# 32-APPLICATION_BOARD_CONNECTOR.net
KiCad netlist of a schematic drawn in Altium Designer
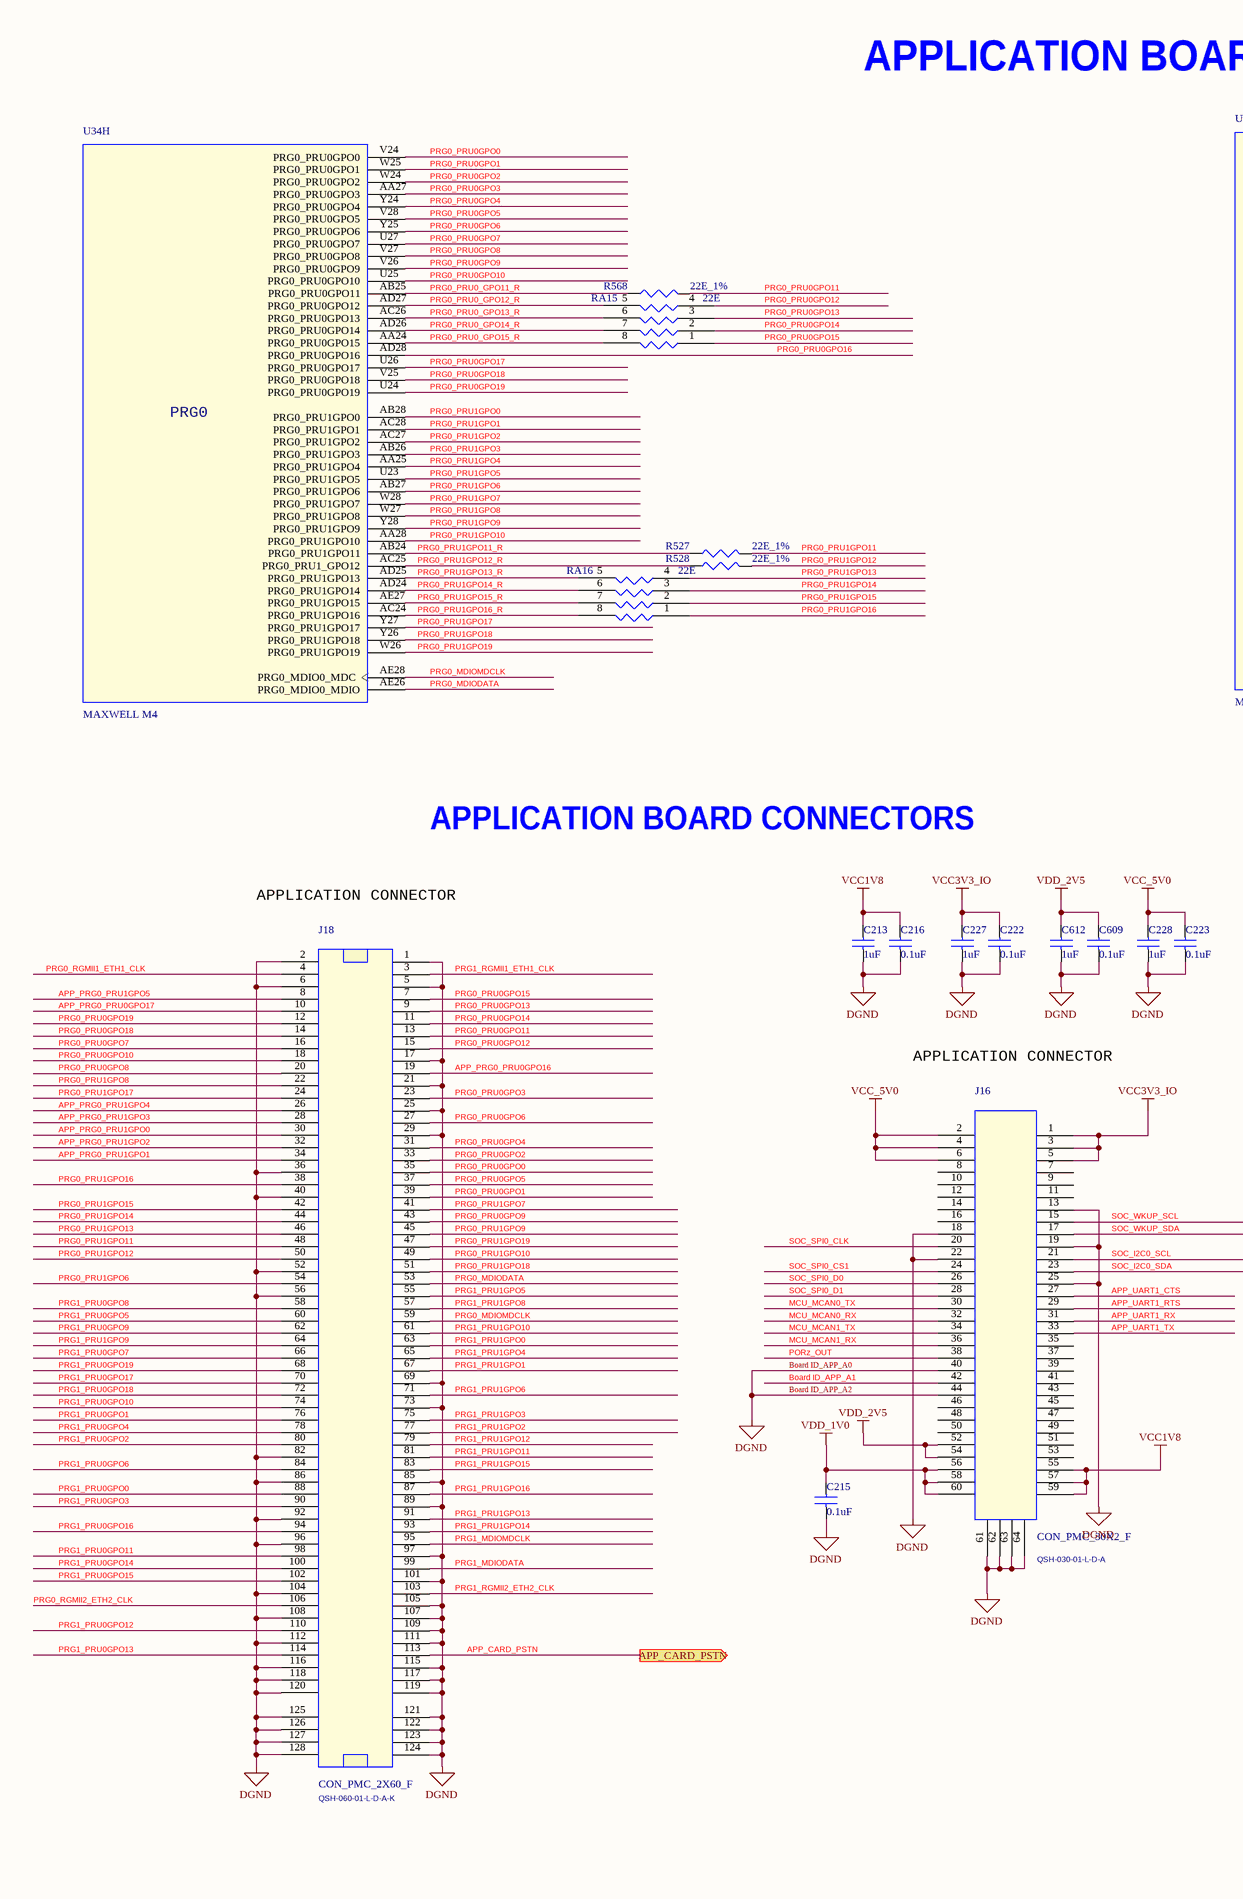
[diagram p0: 32-APPLICATION BOARD CONNECTOR.SchDoc, left]
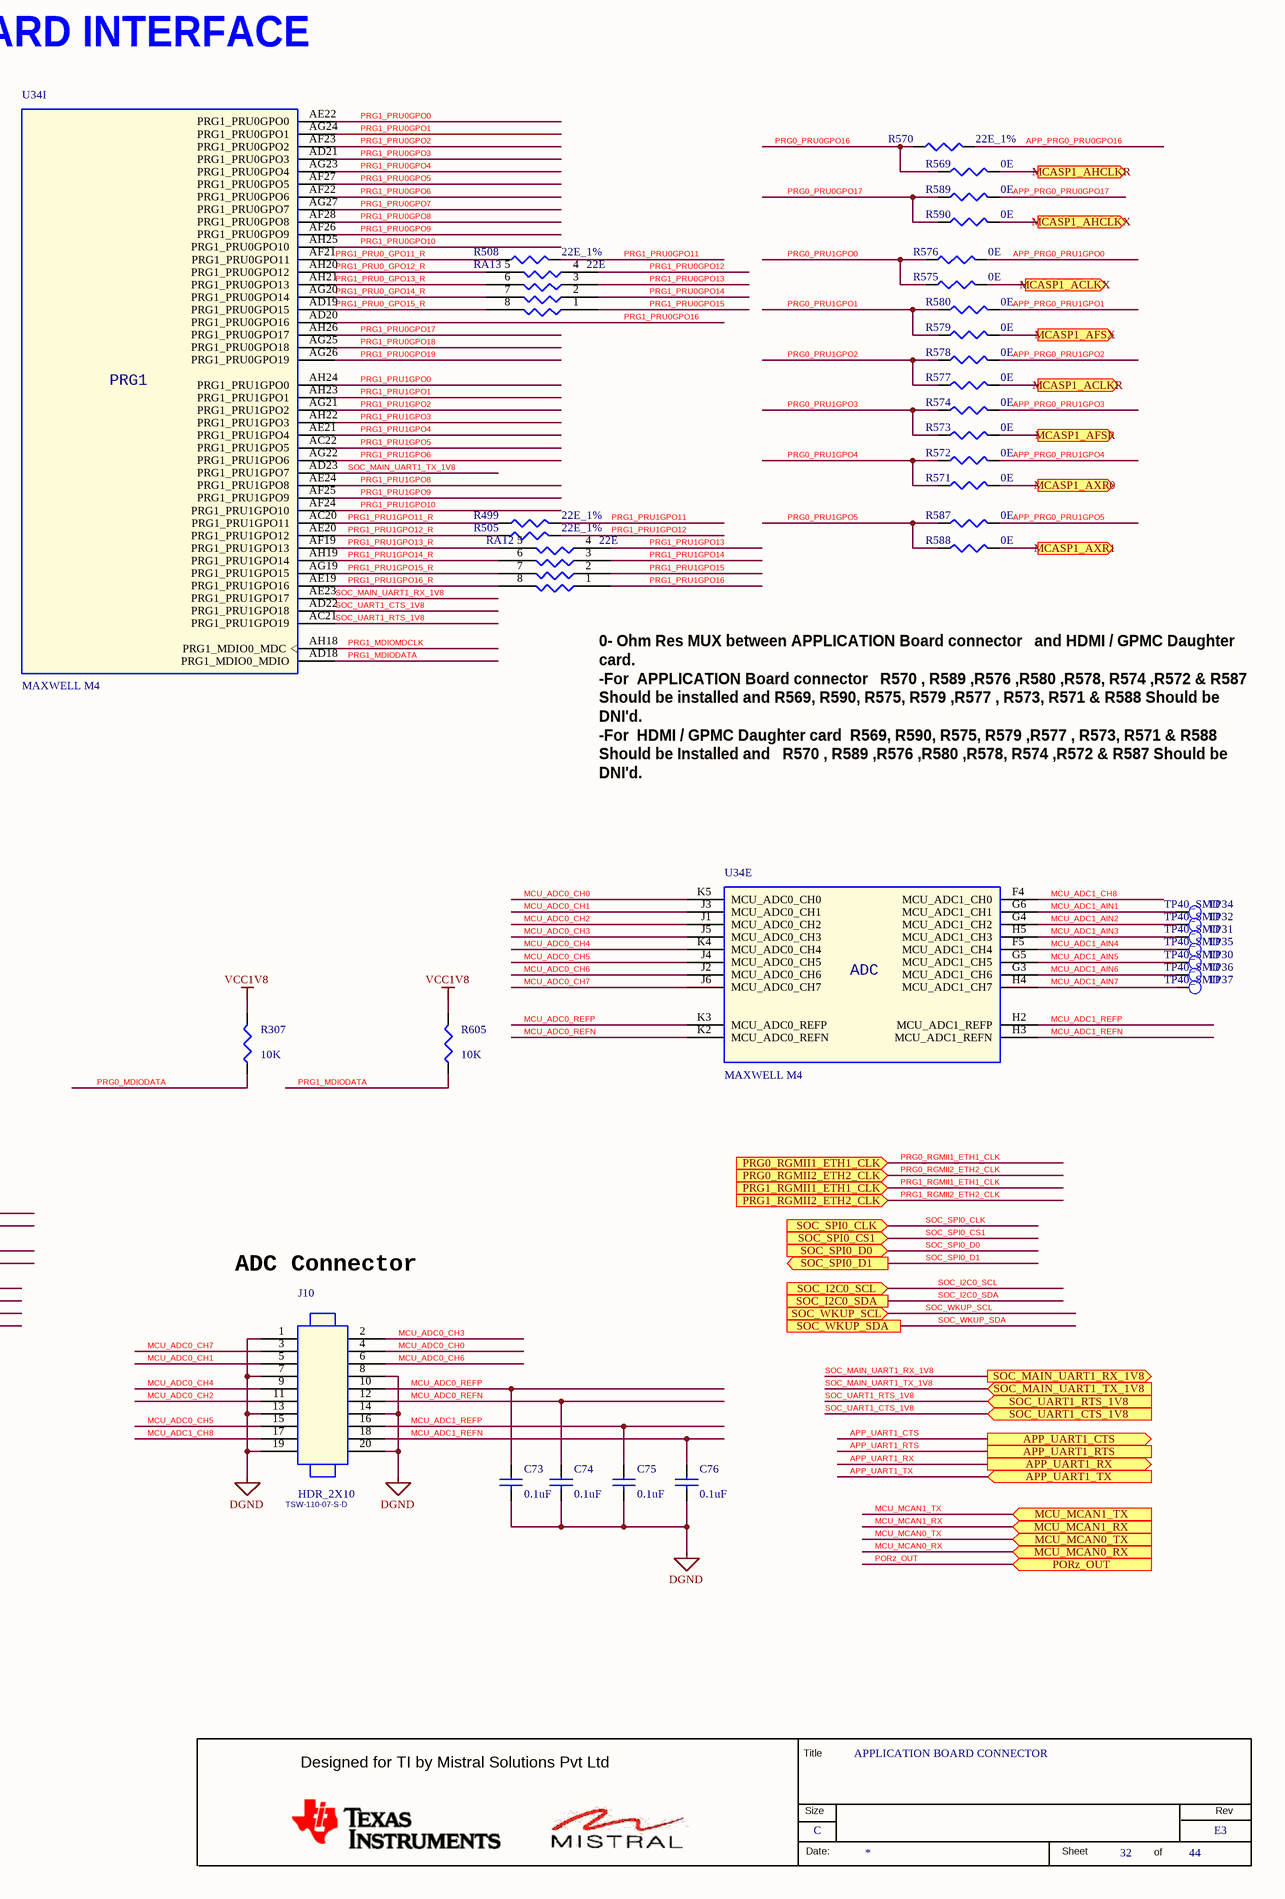
[diagram p1: 32-APPLICATION BOARD CONNECTOR.SchDoc, right]

(export (version "E")
  (design (tool "Eeschema 10.0.6"))
  (components
    (comp (ref "C73")
      (value "0.1uF")
      (footprint "CAP0201_0-5")
      (description "CAP CERAMIC 0.1uF 16V 10% X5R 0201")
      (fields (field (name "DISTRIBUTOR_PART_NUMBER") "490-16742-1-ND") (field (name "VOLTAGE") "16V"))
      (libsource (lib "*") (part "CAP_Dup5"))
    )
    (comp (ref "C74")
      (value "0.1uF")
      (footprint "CAP0201_0-5")
      (description "CAP CERAMIC 0.1uF 16V 10% X5R 0201")
      (fields
        (field (name "MISTRAL PART NO") "120009030072-R")
        (field (name "MFR_PART_NUMBER") "GRM033R61C104KE84J")
      )
      (libsource (lib "*") (part "CAP_Dup5"))
    )
    (comp (ref "C75")
      (value "0.1uF")
      (footprint "CAP0201_0-5")
      (description "CAP CERAMIC 0.1uF 16V 10% X5R 0201")
      (fields (field (name "DISTRIBUTOR_PART_NUMBER") "490-16742-1-ND") (field (name "VOLTAGE") "16V"))
      (libsource (lib "*") (part "CAP_Dup5"))
    )
    (comp (ref "C76")
      (value "0.1uF")
      (footprint "CAP0201_0-5")
      (description "CAP CERAMIC 0.1uF 16V 10% X5R 0201")
      (fields
        (field (name "MISTRAL PART NO") "120009030072-R")
        (field (name "MFR_PART_NUMBER") "GRM033R61C104KE84J")
      )
      (libsource (lib "*") (part "CAP_Dup5"))
    )
    (comp (ref "C213")
      (value "1uF")
      (footprint "CAP0402_0-75")
      (description "CAP CERAMIC 1uF 16V 20% X5R 0402")
      (fields
        (field (name "MISTRAL PART NO") "120018020006-R")
        (field (name "MFR_PART_NUMBER") "EMK105BJ105MV-F")
      )
      (libsource (lib "*") (part "CAP_Dup5"))
    )
    (comp (ref "C215")
      (value "0.1uF")
      (footprint "CAP0201_0-5")
      (description "CAP CERAMIC 0.1uF 16V 10% X5R 0201")
      (fields
        (field (name "MISTRAL PART NO") "120009030072-R")
        (field (name "MFR_PART_NUMBER") "GRM033R61C104KE84J")
      )
      (libsource (lib "*") (part "CAP_Dup5"))
    )
    (comp (ref "C216")
      (value "0.1uF")
      (footprint "CAP0201_0-5")
      (description "CAP CERAMIC 0.1uF 16V 10% X5R 0201")
      (fields (field (name "DISTRIBUTOR_PART_NUMBER") "490-16742-1-ND") (field (name "VOLTAGE") "16V"))
      (libsource (lib "*") (part "CAP_Dup5"))
    )
    (comp (ref "C222")
      (value "0.1uF")
      (footprint "CAP0201_0-5")
      (description "CAP CERAMIC 0.1uF 16V 10% X5R 0201")
      (fields
        (field (name "MISTRAL PART NO") "120009030072-R")
        (field (name "MFR_PART_NUMBER") "GRM033R61C104KE84J")
      )
      (libsource (lib "*") (part "CAP_Dup5"))
    )
    (comp (ref "C223")
      (value "0.1uF")
      (footprint "CAP0201_0-5")
      (description "CAP CERAMIC 0.1uF 16V 10% X5R 0201")
      (fields (field (name "DISTRIBUTOR_PART_NUMBER") "490-16742-1-ND") (field (name "VOLTAGE") "16V"))
      (libsource (lib "*") (part "CAP_Dup5"))
    )
    (comp (ref "C227")
      (value "1uF")
      (footprint "CAP0402_0-75")
      (description "CAP CERAMIC 1uF 16V 20% X5R 0402")
      (fields (field (name "DISTRIBUTOR_PART_NUMBER") "587-5514-1-ND") (field (name "VOLTAGE") "16V"))
      (libsource (lib "*") (part "CAP_Dup5"))
    )
    (comp (ref "C228")
      (value "1uF")
      (footprint "CAP0402_0-75")
      (description "CAP CERAMIC 1uF 16V 20% X5R 0402")
      (fields
        (field (name "MISTRAL PART NO") "120018020006-R")
        (field (name "MFR_PART_NUMBER") "EMK105BJ105MV-F")
      )
      (libsource (lib "*") (part "CAP_Dup5"))
    )
    (comp (ref "C609")
      (value "0.1uF")
      (footprint "CAP0201_0-5")
      (description "CAP CERAMIC 0.1uF 16V 10% X5R 0201")
      (fields
        (field (name "MISTRAL PART NO") "120009030072-R")
        (field (name "MFR_PART_NUMBER") "GRM033R61C104KE84J")
      )
      (libsource (lib "*") (part "CAP_Dup5"))
    )
    (comp (ref "C612")
      (value "1uF")
      (footprint "CAP0402_0-75")
      (description "CAP CERAMIC 1uF 16V 20% X5R 0402")
      (fields
        (field (name "MISTRAL PART NO") "120018020006-R")
        (field (name "MFR_PART_NUMBER") "EMK105BJ105MV-F")
      )
      (libsource (lib "*") (part "CAP_Dup5"))
    )
    (comp (ref "J10")
      (value "HDR_2X10")
      (footprint "HDR_2X10_TSW_100_S_T")
      (description "CON HDR 2X10 2.54MM PITCH ST TH")
      (fields
        (field (name "DISTRIBUTOR_PART_NUMBER") "SAM1032-10-ND")
        (field (name "VOLTAGE") "NA")
        (field (name "MFR_PART_NUMBER") "TSW-110-07-S-D")
      )
      (libsource (lib "*") (part "HEADER_10X2"))
    )
    (comp (ref "J16")
      (value "CON_PMC_30X2_F")
      (footprint "CON_PMC30X2_QSH-030-01-L_S_S_S")
      (description "CON PMC 30X2 0.50MM PITCH FEMALE ST SMD")
      (fields
        (field (name "MISTRAL PART NO") "150009030606")
        (field (name "MFR_PART_NUMBER") "QSH-030-01-L-D-A")
      )
      (libsource (lib "*") (part "CON_PMC_30X2_F_Dup1"))
    )
    (comp (ref "J18")
      (value "CON_PMC_2X60_F")
      (footprint "CON_PMC60X2_HQCD-060_S_S_S_3-3")
      (description "CON PMC 2X60 0.50MM PITCH FEMALE ST SMD")
      (fields
        (field (name "MISTRAL PART NO") "150010060004-R")
        (field (name "MFR_PART_NUMBER") "QSH-060-01-L-D-A-K")
        (field (name "TOLERANCE") "NA")
      )
      (libsource (lib "*") (part "CON_PMC_60X2_HQCD"))
    )
    (comp (ref "R307")
      (value "10K")
      (footprint "RES0402_0-5")
      (description "RES 10K 1/16W 5% 0402")
      (fields
        (field (name "MISTRAL PART NO") "110009030208-R")
        (field (name "MFR_PART_NUMBER") "RC0402JR-0710KL")
      )
      (libsource (lib "*") (part "RESISTOR_Dup5"))
    )
    (comp (ref "R499")
      (value "22E_1%")
      (footprint "RES0402")
      (description "RES 22E 1/16W 1% 0402")
      (fields
        (field (name "MISTRAL PART NO") "110009090004-P")
        (field (name "MFR_PART_NUMBER") "RC0402FR-0722RL")
      )
      (libsource (lib "*") (part "RESISTOR_Dup5"))
    )
    (comp (ref "R505")
      (value "22E_1%")
      (footprint "RES0402")
      (description "RES 22E 1/16W 1% 0402")
      (fields
        (field (name "CUST_PART_NUMBER") "4700-80047E")
        (field (name "DISTRIBUTOR_PART_NUMBER") "311-22.0LRCT-ND")
      )
      (libsource (lib "*") (part "RESISTOR_Dup5"))
    )
    (comp (ref "R508")
      (value "22E_1%")
      (footprint "RES0402")
      (description "RES 22E 1/16W 1% 0402")
      (fields
        (field (name "MISTRAL PART NO") "110009090004-P")
        (field (name "MFR_PART_NUMBER") "RC0402FR-0722RL")
      )
      (libsource (lib "*") (part "RESISTOR_Dup5"))
    )
    (comp (ref "R527")
      (value "22E_1%")
      (footprint "RES0402")
      (description "RES 22E 1/16W 1% 0402")
      (fields
        (field (name "MISTRAL PART NO") "110009090004-P")
        (field (name "MFR_PART_NUMBER") "RC0402FR-0722RL")
      )
      (libsource (lib "*") (part "RESISTOR_Dup5"))
    )
    (comp (ref "R528")
      (value "22E_1%")
      (footprint "RES0402")
      (description "RES 22E 1/16W 1% 0402")
      (fields
        (field (name "MISTRAL PART NO") "110009090004-P")
        (field (name "MFR_PART_NUMBER") "RC0402FR-0722RL")
      )
      (libsource (lib "*") (part "RESISTOR_Dup5"))
    )
    (comp (ref "R568")
      (value "22E_1%")
      (footprint "RES0402")
      (description "RES 22E 1/16W 1% 0402")
      (fields
        (field (name "MISTRAL PART NO") "110009090004-P")
        (field (name "MFR_PART_NUMBER") "RC0402FR-0722RL")
      )
      (libsource (lib "*") (part "RESISTOR_Dup5"))
    )
    (comp (ref "R569")
      (value "0E")
      (footprint "RES0402_0-5")
      (description "RES 0E 1/16W 0402")
      (fields
        (field (name "MISTRAL PART NO") "110010080019-P")
        (field (name "MFR_PART_NUMBER") "CRCW04020000Z0ED")
      )
      (libsource (lib "*") (part "RESISTOR_Dup5"))
    )
    (comp (ref "R570")
      (value "22E_1%")
      (footprint "RES0402")
      (description "RES 22E 1/16W 1% 0402")
      (fields
        (field (name "MISTRAL PART NO") "110009090004-P")
        (field (name "MFR_PART_NUMBER") "RC0402FR-0722RL")
      )
      (libsource (lib "*") (part "RESISTOR_Dup5"))
    )
    (comp (ref "R571")
      (value "0E")
      (footprint "RES0402_0-5")
      (description "RES 0E 1/16W 0402")
      (fields
        (field (name "MISTRAL PART NO") "110010080019-P")
        (field (name "MFR_PART_NUMBER") "CRCW04020000Z0ED")
      )
      (libsource (lib "*") (part "RESISTOR_Dup5"))
    )
    (comp (ref "R572")
      (value "0E")
      (footprint "RES0402_0-5")
      (description "RES 0E 1/16W 0402")
      (fields
        (field (name "MISTRAL PART NO") "110010080019-P")
        (field (name "MFR_PART_NUMBER") "CRCW04020000Z0ED")
      )
      (libsource (lib "*") (part "RESISTOR_Dup5"))
    )
    (comp (ref "R573")
      (value "0E")
      (footprint "RES0402_0-5")
      (description "RES 0E 1/16W 0402")
      (fields (field (name "DISTRIBUTOR_PART_NUMBER") "541-0.0JCT-ND") (field (name "VOLTAGE") "NA"))
      (libsource (lib "*") (part "RESISTOR_Dup5"))
    )
    (comp (ref "R574")
      (value "0E")
      (footprint "RES0402_0-5")
      (description "RES 0E 1/16W 0402")
      (fields (field (name "DISTRIBUTOR_PART_NUMBER") "541-0.0JCT-ND") (field (name "VOLTAGE") "NA"))
      (libsource (lib "*") (part "RESISTOR_Dup5"))
    )
    (comp (ref "R575")
      (value "0E")
      (footprint "RES0402_0-5")
      (description "RES 0E 1/16W 0402")
      (fields (field (name "DISTRIBUTOR_PART_NUMBER") "541-0.0JCT-ND") (field (name "VOLTAGE") "NA"))
      (libsource (lib "*") (part "RESISTOR_Dup5"))
    )
    (comp (ref "R576")
      (value "0E")
      (footprint "RES0402_0-5")
      (description "RES 0E 1/16W 0402")
      (fields (field (name "DISTRIBUTOR_PART_NUMBER") "541-0.0JCT-ND") (field (name "VOLTAGE") "NA"))
      (libsource (lib "*") (part "RESISTOR_Dup5"))
    )
    (comp (ref "R577")
      (value "0E")
      (footprint "RES0402_0-5")
      (description "RES 0E 1/16W 0402")
      (fields
        (field (name "MISTRAL PART NO") "110010080019-P")
        (field (name "MFR_PART_NUMBER") "CRCW04020000Z0ED")
      )
      (libsource (lib "*") (part "RESISTOR_Dup5"))
    )
    (comp (ref "R578")
      (value "0E")
      (footprint "RES0402_0-5")
      (description "RES 0E 1/16W 0402")
      (fields
        (field (name "MISTRAL PART NO") "110010080019-P")
        (field (name "MFR_PART_NUMBER") "CRCW04020000Z0ED")
      )
      (libsource (lib "*") (part "RESISTOR_Dup5"))
    )
    (comp (ref "R579")
      (value "0E")
      (footprint "RES0402_0-5")
      (description "RES 0E 1/16W 0402")
      (fields (field (name "DISTRIBUTOR_PART_NUMBER") "541-0.0JCT-ND") (field (name "VOLTAGE") "NA"))
      (libsource (lib "*") (part "RESISTOR_Dup5"))
    )
    (comp (ref "R580")
      (value "0E")
      (footprint "RES0402_0-5")
      (description "RES 0E 1/16W 0402")
      (fields (field (name "DISTRIBUTOR_PART_NUMBER") "541-0.0JCT-ND") (field (name "VOLTAGE") "NA"))
      (libsource (lib "*") (part "RESISTOR_Dup5"))
    )
    (comp (ref "R587")
      (value "0E")
      (footprint "RES0402_0-5")
      (description "RES 0E 1/16W 0402")
      (fields (field (name "DISTRIBUTOR_PART_NUMBER") "541-0.0JCT-ND") (field (name "VOLTAGE") "NA"))
      (libsource (lib "*") (part "RESISTOR_Dup5"))
    )
    (comp (ref "R588")
      (value "0E")
      (footprint "RES0402_0-5")
      (description "RES 0E 1/16W 0402")
      (fields (field (name "DISTRIBUTOR_PART_NUMBER") "541-0.0JCT-ND") (field (name "VOLTAGE") "NA"))
      (libsource (lib "*") (part "RESISTOR_Dup5"))
    )
    (comp (ref "R589")
      (value "0E")
      (footprint "RES0402_0-5")
      (description "RES 0E 1/16W 0402")
      (fields
        (field (name "MISTRAL PART NO") "110010080019-P")
        (field (name "MFR_PART_NUMBER") "CRCW04020000Z0ED")
      )
      (libsource (lib "*") (part "RESISTOR_Dup5"))
    )
    (comp (ref "R590")
      (value "0E")
      (footprint "RES0402_0-5")
      (description "RES 0E 1/16W 0402")
      (fields
        (field (name "MISTRAL PART NO") "110010080019-P")
        (field (name "MFR_PART_NUMBER") "CRCW04020000Z0ED")
      )
      (libsource (lib "*") (part "RESISTOR_Dup5"))
    )
    (comp (ref "R605")
      (value "10K")
      (footprint "RES0402_0-5")
      (description "RES 10K 1/16W 5% 0402")
      (fields
        (field (name "MISTRAL PART NO") "110009030208-R")
        (field (name "MFR_PART_NUMBER") "RC0402JR-0710KL")
      )
      (libsource (lib "*") (part "RESISTOR_Dup5"))
    )
    (comp (ref "RA12")
      (value "22E")
      (footprint "RESA_EXB28V_0402-4_0-5")
      (description "RES ARRAY 22E 31mW 5% 0402")
      (fields
        (field (name "MISTRAL PART NO") "110009030021-R")
        (field (name "MFR_PART_NUMBER") "EXB-28V220JX")
      )
      (libsource (lib "*") (part "RESARR_ISO4"))
    )
    (comp (ref "RA13")
      (value "22E")
      (footprint "RESA_EXB28V_0402-4_0-5")
      (description "RES ARRAY 22E 31mW 5% 0402")
      (fields (field (name "DISTRIBUTOR_PART_NUMBER") "Y7220CT-ND") (field (name "VOLTAGE") "NA"))
      (libsource (lib "*") (part "RESARR_ISO4"))
    )
    (comp (ref "RA15")
      (value "22E")
      (footprint "RESA_EXB28V_0402-4_0-5")
      (description "RES ARRAY 22E 31mW 5% 0402")
      (fields
        (field (name "MISTRAL PART NO") "110009030021-R")
        (field (name "MFR_PART_NUMBER") "EXB-28V220JX")
      )
      (libsource (lib "*") (part "RESARR_ISO4"))
    )
    (comp (ref "RA16")
      (value "22E")
      (footprint "RESA_EXB28V_0402-4_0-5")
      (description "RES ARRAY 22E 31mW 5% 0402")
      (fields
        (field (name "MISTRAL PART NO") "110009030021-R")
        (field (name "MFR_PART_NUMBER") "EXB-28V220JX")
      )
      (libsource (lib "*") (part "RESARR_ISO4"))
    )
    (comp (ref "TP30")
      (value "TP40_SMD")
      (footprint "TP40_SMD")
      (description "TESTPOINT CIR 40 SMD")
      (fields (field (name "VOLTAGE") "NA") (field (name "MISTRAL PART NO") "130009030933"))
      (libsource (lib "*") (part "TESTPOINT"))
    )
    (comp (ref "TP31")
      (value "TP40_SMD")
      (footprint "TP40_SMD")
      (description "TESTPOINT CIR 40 SMD")
      (fields (field (name "VOLTAGE") "NA") (field (name "MISTRAL PART NO") "130009030933"))
      (libsource (lib "*") (part "TESTPOINT"))
    )
    (comp (ref "TP32")
      (value "TP40_SMD")
      (footprint "TP40_SMD")
      (description "TESTPOINT CIR 40 SMD")
      (fields (field (name "DISTRIBUTOR_PART_NUMBER") "NA") (field (name "MISTRAL PART NO") "130009030933"))
      (libsource (lib "*") (part "TESTPOINT"))
    )
    (comp (ref "TP34")
      (value "TP40_SMD")
      (footprint "TP40_SMD")
      (description "TESTPOINT CIR 40 SMD")
      (fields (field (name "VOLTAGE") "NA") (field (name "MISTRAL PART NO") "130009030933"))
      (libsource (lib "*") (part "TESTPOINT"))
    )
    (comp (ref "TP35")
      (value "TP40_SMD")
      (footprint "TP40_SMD")
      (description "TESTPOINT CIR 40 SMD")
      (fields (field (name "DISTRIBUTOR_PART_NUMBER") "NA") (field (name "MISTRAL PART NO") "130009030933"))
      (libsource (lib "*") (part "TESTPOINT"))
    )
    (comp (ref "TP36")
      (value "TP40_SMD")
      (footprint "TP40_SMD")
      (description "TESTPOINT CIR 40 SMD")
      (fields (field (name "VOLTAGE") "NA") (field (name "MISTRAL PART NO") "130009030933"))
      (libsource (lib "*") (part "TESTPOINT"))
    )
    (comp (ref "TP37")
      (value "TP40_SMD")
      (footprint "TP40_SMD")
      (description "TESTPOINT CIR 40 SMD")
      (fields (field (name "DISTRIBUTOR_PART_NUMBER") "NA") (field (name "MISTRAL PART NO") "130009030933"))
      (libsource (lib "*") (part "TESTPOINT"))
    )
    (comp (ref "U34")
      (value "MAXWELL M4")
      (footprint "BGA784_31-49_910X910_1-7")
      (description "IC MAXWELL MICRO CONTROLLER UNIT BGA784")
      (fields
        (field (name "MISTRAL PART NO") "141217100003")
        (field (name "MFR_PART_NUMBER") "MAXWELL M4_EVM")
      )
      (libsource (lib "*") (part "AM654X_BGA784"))
    )
  )
  (nets
    (net (code "1") (name "/APP_CARD_PSTN") (class "Default")
      (node (ref "J18") (pin "113") (pinfunction "113_113") (pintype "passive"))
    )
    (net (code "2") (name "/APP_PRG0_PRU0GPO16") (class "Default")
      (node (ref "J18") (pin "19") (pinfunction "19_19") (pintype "passive"))
      (node (ref "R570") (pin "2") (pinfunction "2_2") (pintype "passive"))
    )
    (net (code "3") (name "/APP_PRG0_PRU0GPO17") (class "Default")
      (node (ref "J18") (pin "10") (pinfunction "10_10") (pintype "passive"))
      (node (ref "R589") (pin "2") (pinfunction "2_2") (pintype "passive"))
    )
    (net (code "4") (name "/APP_PRG0_PRU1GPO0") (class "Default")
      (node (ref "J18") (pin "30") (pinfunction "30_30") (pintype "passive"))
      (node (ref "R576") (pin "2") (pinfunction "2_2") (pintype "passive"))
    )
    (net (code "5") (name "/APP_PRG0_PRU1GPO1") (class "Default")
      (node (ref "J18") (pin "34") (pinfunction "34_34") (pintype "passive"))
      (node (ref "R580") (pin "2") (pinfunction "2_2") (pintype "passive"))
    )
    (net (code "6") (name "/APP_PRG0_PRU1GPO2") (class "Default")
      (node (ref "J18") (pin "32") (pinfunction "32_32") (pintype "passive"))
      (node (ref "R578") (pin "2") (pinfunction "2_2") (pintype "passive"))
    )
    (net (code "7") (name "/APP_PRG0_PRU1GPO3") (class "Default")
      (node (ref "J18") (pin "28") (pinfunction "28_28") (pintype "passive"))
      (node (ref "R574") (pin "2") (pinfunction "2_2") (pintype "passive"))
    )
    (net (code "8") (name "/APP_PRG0_PRU1GPO4") (class "Default")
      (node (ref "J18") (pin "26") (pinfunction "26_26") (pintype "passive"))
      (node (ref "R572") (pin "2") (pinfunction "2_2") (pintype "passive"))
    )
    (net (code "9") (name "/APP_PRG0_PRU1GPO5") (class "Default")
      (node (ref "J18") (pin "8") (pinfunction "8_8") (pintype "passive"))
      (node (ref "R587") (pin "2") (pinfunction "2_2") (pintype "passive"))
    )
    (net (code "10") (name "/APP_UART1_CTS") (class "Default")
      (node (ref "J16") (pin "27") (pinfunction "27_27") (pintype "passive"))
    )
    (net (code "11") (name "/APP_UART1_RTS") (class "Default")
      (node (ref "J16") (pin "29") (pinfunction "29_29") (pintype "passive"))
    )
    (net (code "12") (name "/APP_UART1_RX") (class "Default")
      (node (ref "J16") (pin "31") (pinfunction "31_31") (pintype "passive"))
    )
    (net (code "13") (name "/APP_UART1_TX") (class "Default")
      (node (ref "J16") (pin "33") (pinfunction "33_33") (pintype "passive"))
    )
    (net (code "14") (name "/Board ID_APP_A1") (class "Default")
      (node (ref "J16") (pin "42") (pinfunction "42_42") (pintype "passive"))
    )
    (net (code "15") (name "/MCASP1_ACLKR") (class "Default")
      (node (ref "R577") (pin "2") (pinfunction "2_2") (pintype "passive"))
    )
    (net (code "16") (name "/MCASP1_ACLKX") (class "Default")
      (node (ref "R575") (pin "2") (pinfunction "2_2") (pintype "passive"))
    )
    (net (code "17") (name "/MCASP1_AFSR") (class "Default")
      (node (ref "R573") (pin "2") (pinfunction "2_2") (pintype "passive"))
    )
    (net (code "18") (name "/MCASP1_AFSX") (class "Default")
      (node (ref "R579") (pin "2") (pinfunction "2_2") (pintype "passive"))
    )
    (net (code "19") (name "/MCASP1_AHCLKR") (class "Default")
      (node (ref "R569") (pin "2") (pinfunction "2_2") (pintype "passive"))
    )
    (net (code "20") (name "/MCASP1_AHCLKX") (class "Default")
      (node (ref "R590") (pin "2") (pinfunction "2_2") (pintype "passive"))
    )
    (net (code "21") (name "/MCASP1_AXR0") (class "Default")
      (node (ref "R571") (pin "2") (pinfunction "2_2") (pintype "passive"))
    )
    (net (code "22") (name "/MCASP1_AXR1") (class "Default")
      (node (ref "R588") (pin "2") (pinfunction "2_2") (pintype "passive"))
    )
    (net (code "23") (name "/MCU_ADC0_CH0") (class "Default")
      (node (ref "J10") (pin "4") (pinfunction "4_4") (pintype "passive"))
      (node (ref "U34") (pin "K5") (pinfunction "MCU_ADC0_CH0_K5") (pintype "passive"))
    )
    (net (code "24") (name "/MCU_ADC0_CH1") (class "Default")
      (node (ref "J10") (pin "5") (pinfunction "5_5") (pintype "passive"))
      (node (ref "U34") (pin "J3") (pinfunction "MCU_ADC0_CH1_J3") (pintype "passive"))
    )
    (net (code "25") (name "/MCU_ADC0_CH2") (class "Default")
      (node (ref "J10") (pin "11") (pinfunction "11_11") (pintype "passive"))
      (node (ref "U34") (pin "J1") (pinfunction "MCU_ADC0_CH2_J1") (pintype "passive"))
    )
    (net (code "26") (name "/MCU_ADC0_CH3") (class "Default")
      (node (ref "J10") (pin "2") (pinfunction "2_2") (pintype "passive"))
      (node (ref "U34") (pin "J5") (pinfunction "MCU_ADC0_CH3_J5") (pintype "passive"))
    )
    (net (code "27") (name "/MCU_ADC0_CH4") (class "Default")
      (node (ref "J10") (pin "9") (pinfunction "9_9") (pintype "passive"))
      (node (ref "U34") (pin "K4") (pinfunction "MCU_ADC0_CH4_K4") (pintype "passive"))
    )
    (net (code "28") (name "/MCU_ADC0_CH5") (class "Default")
      (node (ref "J10") (pin "15") (pinfunction "15_15") (pintype "passive"))
      (node (ref "U34") (pin "J4") (pinfunction "MCU_ADC0_CH5_J4") (pintype "passive"))
    )
    (net (code "29") (name "/MCU_ADC0_CH6") (class "Default")
      (node (ref "J10") (pin "6") (pinfunction "6_6") (pintype "passive"))
      (node (ref "U34") (pin "J2") (pinfunction "MCU_ADC0_CH6_J2") (pintype "passive"))
    )
    (net (code "30") (name "/MCU_ADC0_CH7") (class "Default")
      (node (ref "J10") (pin "3") (pinfunction "3_3") (pintype "passive"))
      (node (ref "U34") (pin "J6") (pinfunction "MCU_ADC0_CH7_J6") (pintype "passive"))
    )
    (net (code "31") (name "/MCU_ADC0_REFN") (class "Default")
      (node (ref "C74") (pin "1") (pinfunction "1_1") (pintype "passive"))
      (node (ref "J10") (pin "12") (pinfunction "12_12") (pintype "passive"))
      (node (ref "U34") (pin "K2") (pinfunction "MCU_ADC0_REFN_K2") (pintype "passive"))
    )
    (net (code "32") (name "/MCU_ADC0_REFP") (class "Default")
      (node (ref "C73") (pin "1") (pinfunction "1_1") (pintype "passive"))
      (node (ref "J10") (pin "10") (pinfunction "10_10") (pintype "passive"))
      (node (ref "U34") (pin "K3") (pinfunction "MCU_ADC0_REFP_K3") (pintype "passive"))
    )
    (net (code "33") (name "/MCU_ADC1_AIN1") (class "Default")
      (node (ref "TP34") (pin "1") (pinfunction "TP_1") (pintype "passive"))
      (node (ref "U34") (pin "G6") (pinfunction "MCU_ADC1_CH1_G6") (pintype "passive"))
    )
    (net (code "34") (name "/MCU_ADC1_AIN2") (class "Default")
      (node (ref "TP32") (pin "1") (pinfunction "TP_1") (pintype "passive"))
      (node (ref "U34") (pin "G4") (pinfunction "MCU_ADC1_CH2_G4") (pintype "passive"))
    )
    (net (code "35") (name "/MCU_ADC1_AIN3") (class "Default")
      (node (ref "TP31") (pin "1") (pinfunction "TP_1") (pintype "passive"))
      (node (ref "U34") (pin "H5") (pinfunction "MCU_ADC1_CH3_H5") (pintype "passive"))
    )
    (net (code "36") (name "/MCU_ADC1_AIN4") (class "Default")
      (node (ref "TP35") (pin "1") (pinfunction "TP_1") (pintype "passive"))
      (node (ref "U34") (pin "F5") (pinfunction "MCU_ADC1_CH4_F5") (pintype "passive"))
    )
    (net (code "37") (name "/MCU_ADC1_AIN5") (class "Default")
      (node (ref "TP30") (pin "1") (pinfunction "TP_1") (pintype "passive"))
      (node (ref "U34") (pin "G5") (pinfunction "MCU_ADC1_CH5_G5") (pintype "passive"))
    )
    (net (code "38") (name "/MCU_ADC1_AIN6") (class "Default")
      (node (ref "TP36") (pin "1") (pinfunction "TP_1") (pintype "passive"))
      (node (ref "U34") (pin "G3") (pinfunction "MCU_ADC1_CH6_G3") (pintype "passive"))
    )
    (net (code "39") (name "/MCU_ADC1_AIN7") (class "Default")
      (node (ref "TP37") (pin "1") (pinfunction "TP_1") (pintype "passive"))
      (node (ref "U34") (pin "H4") (pinfunction "MCU_ADC1_CH7_H4") (pintype "passive"))
    )
    (net (code "40") (name "/MCU_ADC1_CH8") (class "Default")
      (node (ref "J10") (pin "17") (pinfunction "17_17") (pintype "passive"))
      (node (ref "U34") (pin "F4") (pinfunction "MCU_ADC1_CH0_F4") (pintype "passive"))
    )
    (net (code "41") (name "/MCU_ADC1_REFN") (class "Default")
      (node (ref "C76") (pin "1") (pinfunction "1_1") (pintype "passive"))
      (node (ref "J10") (pin "18") (pinfunction "18_18") (pintype "passive"))
      (node (ref "U34") (pin "H3") (pinfunction "MCU_ADC1_REFN_H3") (pintype "passive"))
    )
    (net (code "42") (name "/MCU_ADC1_REFP") (class "Default")
      (node (ref "C75") (pin "1") (pinfunction "1_1") (pintype "passive"))
      (node (ref "J10") (pin "16") (pinfunction "16_16") (pintype "passive"))
      (node (ref "U34") (pin "H2") (pinfunction "MCU_ADC1_REFP_H2") (pintype "passive"))
    )
    (net (code "43") (name "/MCU_MCAN0_RX") (class "Default")
      (node (ref "J16") (pin "32") (pinfunction "32_32") (pintype "passive"))
    )
    (net (code "44") (name "/MCU_MCAN0_TX") (class "Default")
      (node (ref "J16") (pin "30") (pinfunction "30_30") (pintype "passive"))
    )
    (net (code "45") (name "/MCU_MCAN1_RX") (class "Default")
      (node (ref "J16") (pin "36") (pinfunction "36_36") (pintype "passive"))
    )
    (net (code "46") (name "/MCU_MCAN1_TX") (class "Default")
      (node (ref "J16") (pin "34") (pinfunction "34_34") (pintype "passive"))
    )
    (net (code "47") (name "/PORz_OUT") (class "Default")
      (node (ref "J16") (pin "38") (pinfunction "38_38") (pintype "passive"))
    )
    (net (code "48") (name "/PRG0_MDIODATA") (class "Default")
      (node (ref "J18") (pin "53") (pinfunction "53_53") (pintype "passive"))
      (node (ref "R307") (pin "1") (pinfunction "1_1") (pintype "passive"))
      (node (ref "U34") (pin "AE26") (pinfunction "PRG0_MDIO0_MDIO_AE26") (pintype "passive"))
    )
    (net (code "49") (name "/PRG0_MDIOMDCLK") (class "Default")
      (node (ref "J18") (pin "59") (pinfunction "59_59") (pintype "passive"))
      (node (ref "U34") (pin "AE28") (pinfunction "PRG0_MDIO0_MDC_AE28") (pintype "passive"))
    )
    (net (code "50") (name "/PRG0_PRU0GPO0") (class "Default")
      (node (ref "J18") (pin "35") (pinfunction "35_35") (pintype "passive"))
      (node (ref "U34") (pin "V24") (pinfunction "PRG0_PRU0GPO0_V24") (pintype "passive"))
    )
    (net (code "51") (name "/PRG0_PRU0GPO1") (class "Default")
      (node (ref "J18") (pin "39") (pinfunction "39_39") (pintype "passive"))
      (node (ref "U34") (pin "W25") (pinfunction "PRG0_PRU0GPO1_W25") (pintype "passive"))
    )
    (net (code "52") (name "/PRG0_PRU0GPO2") (class "Default")
      (node (ref "J18") (pin "33") (pinfunction "33_33") (pintype "passive"))
      (node (ref "U34") (pin "W24") (pinfunction "PRG0_PRU0GPO2_W24") (pintype "passive"))
    )
    (net (code "53") (name "/PRG0_PRU0GPO3") (class "Default")
      (node (ref "J18") (pin "23") (pinfunction "23_23") (pintype "passive"))
      (node (ref "U34") (pin "AA27") (pinfunction "PRG0_PRU0GPO3_AA27") (pintype "passive"))
    )
    (net (code "54") (name "/PRG0_PRU0GPO4") (class "Default")
      (node (ref "J18") (pin "31") (pinfunction "31_31") (pintype "passive"))
      (node (ref "U34") (pin "Y24") (pinfunction "PRG0_PRU0GPO4_Y24") (pintype "passive"))
    )
    (net (code "55") (name "/PRG0_PRU0GPO5") (class "Default")
      (node (ref "J18") (pin "37") (pinfunction "37_37") (pintype "passive"))
      (node (ref "U34") (pin "V28") (pinfunction "PRG0_PRU0GPO5_V28") (pintype "passive"))
    )
    (net (code "56") (name "/PRG0_PRU0GPO6") (class "Default")
      (node (ref "J18") (pin "27") (pinfunction "27_27") (pintype "passive"))
      (node (ref "U34") (pin "Y25") (pinfunction "PRG0_PRU0GPO6_Y25") (pintype "passive"))
    )
    (net (code "57") (name "/PRG0_PRU0GPO7") (class "Default")
      (node (ref "J18") (pin "16") (pinfunction "16_16") (pintype "passive"))
      (node (ref "U34") (pin "U27") (pinfunction "PRG0_PRU0GPO7_U27") (pintype "passive"))
    )
    (net (code "58") (name "/PRG0_PRU0GPO8") (class "Default")
      (node (ref "J18") (pin "20") (pinfunction "20_20") (pintype "passive"))
      (node (ref "U34") (pin "V27") (pinfunction "PRG0_PRU0GPO8_V27") (pintype "passive"))
    )
    (net (code "59") (name "/PRG0_PRU0GPO9") (class "Default")
      (node (ref "J18") (pin "43") (pinfunction "43_43") (pintype "passive"))
      (node (ref "U34") (pin "V26") (pinfunction "PRG0_PRU0GPO9_V26") (pintype "passive"))
    )
    (net (code "60") (name "/PRG0_PRU0GPO10") (class "Default")
      (node (ref "J18") (pin "18") (pinfunction "18_18") (pintype "passive"))
      (node (ref "U34") (pin "U25") (pinfunction "PRG0_PRU0GPO10_U25") (pintype "passive"))
    )
    (net (code "61") (name "/PRG0_PRU0GPO11") (class "Default")
      (node (ref "J18") (pin "13") (pinfunction "13_13") (pintype "passive"))
      (node (ref "R568") (pin "2") (pinfunction "2_2") (pintype "passive"))
    )
    (net (code "62") (name "/PRG0_PRU0GPO12") (class "Default")
      (node (ref "J18") (pin "15") (pinfunction "15_15") (pintype "passive"))
      (node (ref "RA15") (pin "4") (pinfunction "4_4") (pintype "passive"))
    )
    (net (code "63") (name "/PRG0_PRU0GPO13") (class "Default")
      (node (ref "J18") (pin "9") (pinfunction "9_9") (pintype "passive"))
      (node (ref "RA15") (pin "3") (pinfunction "3_3") (pintype "passive"))
    )
    (net (code "64") (name "/PRG0_PRU0GPO14") (class "Default")
      (node (ref "J18") (pin "11") (pinfunction "11_11") (pintype "passive"))
      (node (ref "RA15") (pin "2") (pinfunction "2_2") (pintype "passive"))
    )
    (net (code "65") (name "/PRG0_PRU0GPO15") (class "Default")
      (node (ref "J18") (pin "7") (pinfunction "7_7") (pintype "passive"))
      (node (ref "RA15") (pin "1") (pinfunction "1_1") (pintype "passive"))
    )
    (net (code "66") (name "/PRG0_PRU0GPO16") (class "Default")
      (node (ref "R569") (pin "1") (pinfunction "1_1") (pintype "passive"))
      (node (ref "R570") (pin "1") (pinfunction "1_1") (pintype "passive"))
      (node (ref "U34") (pin "AD28") (pinfunction "PRG0_PRU0GPO16_AD28") (pintype "passive"))
    )
    (net (code "67") (name "/PRG0_PRU0GPO17") (class "Default")
      (node (ref "R589") (pin "1") (pinfunction "1_1") (pintype "passive"))
      (node (ref "R590") (pin "1") (pinfunction "1_1") (pintype "passive"))
      (node (ref "U34") (pin "U26") (pinfunction "PRG0_PRU0GPO17_U26") (pintype "passive"))
    )
    (net (code "68") (name "/PRG0_PRU0GPO18") (class "Default")
      (node (ref "J18") (pin "14") (pinfunction "14_14") (pintype "passive"))
      (node (ref "U34") (pin "V25") (pinfunction "PRG0_PRU0GPO18_V25") (pintype "passive"))
    )
    (net (code "69") (name "/PRG0_PRU0GPO19") (class "Default")
      (node (ref "J18") (pin "12") (pinfunction "12_12") (pintype "passive"))
      (node (ref "U34") (pin "U24") (pinfunction "PRG0_PRU0GPO19_U24") (pintype "passive"))
    )
    (net (code "70") (name "/PRG0_PRU0_GPO11_R") (class "Default")
      (node (ref "R568") (pin "1") (pinfunction "1_1") (pintype "passive"))
      (node (ref "U34") (pin "AB25") (pinfunction "PRG0_PRU0GPO11_AB25") (pintype "passive"))
    )
    (net (code "71") (name "/PRG0_PRU0_GPO12_R") (class "Default")
      (node (ref "RA15") (pin "5") (pinfunction "5_5") (pintype "passive"))
      (node (ref "U34") (pin "AD27") (pinfunction "PRG0_PRU0GPO12_AD27") (pintype "passive"))
    )
    (net (code "72") (name "/PRG0_PRU0_GPO13_R") (class "Default")
      (node (ref "RA15") (pin "6") (pinfunction "6_6") (pintype "passive"))
      (node (ref "U34") (pin "AC26") (pinfunction "PRG0_PRU0GPO13_AC26") (pintype "passive"))
    )
    (net (code "73") (name "/PRG0_PRU0_GPO14_R") (class "Default")
      (node (ref "RA15") (pin "7") (pinfunction "7_7") (pintype "passive"))
      (node (ref "U34") (pin "AD26") (pinfunction "PRG0_PRU0GPO14_AD26") (pintype "passive"))
    )
    (net (code "74") (name "/PRG0_PRU0_GPO15_R") (class "Default")
      (node (ref "RA15") (pin "8") (pinfunction "8_8") (pintype "passive"))
      (node (ref "U34") (pin "AA24") (pinfunction "PRG0_PRU0GPO15_AA24") (pintype "passive"))
    )
    (net (code "75") (name "/PRG0_PRU1GPO0") (class "Default")
      (node (ref "R575") (pin "1") (pinfunction "1_1") (pintype "passive"))
      (node (ref "R576") (pin "1") (pinfunction "1_1") (pintype "passive"))
      (node (ref "U34") (pin "AB28") (pinfunction "PRG0_PRU1GPO0_AB28") (pintype "passive"))
    )
    (net (code "76") (name "/PRG0_PRU1GPO1") (class "Default")
      (node (ref "R579") (pin "1") (pinfunction "1_1") (pintype "passive"))
      (node (ref "R580") (pin "1") (pinfunction "1_1") (pintype "passive"))
      (node (ref "U34") (pin "AC28") (pinfunction "PRG0_PRU1GPO1_AC28") (pintype "passive"))
    )
    (net (code "77") (name "/PRG0_PRU1GPO2") (class "Default")
      (node (ref "R577") (pin "1") (pinfunction "1_1") (pintype "passive"))
      (node (ref "R578") (pin "1") (pinfunction "1_1") (pintype "passive"))
      (node (ref "U34") (pin "AC27") (pinfunction "PRG0_PRU1GPO2_AC27") (pintype "passive"))
    )
    (net (code "78") (name "/PRG0_PRU1GPO3") (class "Default")
      (node (ref "R573") (pin "1") (pinfunction "1_1") (pintype "passive"))
      (node (ref "R574") (pin "1") (pinfunction "1_1") (pintype "passive"))
      (node (ref "U34") (pin "AB26") (pinfunction "PRG0_PRU1GPO3_AB26") (pintype "passive"))
    )
    (net (code "79") (name "/PRG0_PRU1GPO4") (class "Default")
      (node (ref "R571") (pin "1") (pinfunction "1_1") (pintype "passive"))
      (node (ref "R572") (pin "1") (pinfunction "1_1") (pintype "passive"))
      (node (ref "U34") (pin "AA25") (pinfunction "PRG0_PRU1GPO4_AA25") (pintype "passive"))
    )
    (net (code "80") (name "/PRG0_PRU1GPO5") (class "Default")
      (node (ref "R587") (pin "1") (pinfunction "1_1") (pintype "passive"))
      (node (ref "R588") (pin "1") (pinfunction "1_1") (pintype "passive"))
      (node (ref "U34") (pin "U23") (pinfunction "PRG0_PRU1GPO5_U23") (pintype "passive"))
    )
    (net (code "81") (name "/PRG0_PRU1GPO6") (class "Default")
      (node (ref "J18") (pin "54") (pinfunction "54_54") (pintype "passive"))
      (node (ref "U34") (pin "AB27") (pinfunction "PRG0_PRU1GPO6_AB27") (pintype "passive"))
    )
    (net (code "82") (name "/PRG0_PRU1GPO7") (class "Default")
      (node (ref "J18") (pin "41") (pinfunction "41_41") (pintype "passive"))
      (node (ref "U34") (pin "W28") (pinfunction "PRG0_PRU1GPO7_W28") (pintype "passive"))
    )
    (net (code "83") (name "/PRG0_PRU1GPO8") (class "Default")
      (node (ref "J18") (pin "22") (pinfunction "22_22") (pintype "passive"))
      (node (ref "U34") (pin "W27") (pinfunction "PRG0_PRU1GPO8_W27") (pintype "passive"))
    )
    (net (code "84") (name "/PRG0_PRU1GPO9") (class "Default")
      (node (ref "J18") (pin "45") (pinfunction "45_45") (pintype "passive"))
      (node (ref "U34") (pin "Y28") (pinfunction "PRG0_PRU1GPO9_Y28") (pintype "passive"))
    )
    (net (code "85") (name "/PRG0_PRU1GPO10") (class "Default")
      (node (ref "J18") (pin "49") (pinfunction "49_49") (pintype "passive"))
      (node (ref "U34") (pin "AA28") (pinfunction "PRG0_PRU1GPO10_AA28") (pintype "passive"))
    )
    (net (code "86") (name "/PRG0_PRU1GPO11") (class "Default")
      (node (ref "J18") (pin "48") (pinfunction "48_48") (pintype "passive"))
      (node (ref "R527") (pin "2") (pinfunction "2_2") (pintype "passive"))
    )
    (net (code "87") (name "/PRG0_PRU1GPO11_R") (class "Default")
      (node (ref "R527") (pin "1") (pinfunction "1_1") (pintype "passive"))
      (node (ref "U34") (pin "AB24") (pinfunction "PRG0_PRU1GPO11_AB24") (pintype "passive"))
    )
    (net (code "88") (name "/PRG0_PRU1GPO12") (class "Default")
      (node (ref "J18") (pin "50") (pinfunction "50_50") (pintype "passive"))
      (node (ref "R528") (pin "2") (pinfunction "2_2") (pintype "passive"))
    )
    (net (code "89") (name "/PRG0_PRU1GPO12_R") (class "Default")
      (node (ref "R528") (pin "1") (pinfunction "1_1") (pintype "passive"))
      (node (ref "U34") (pin "AC25") (pinfunction "PRG0_PRU1_GPO12_AC25") (pintype "passive"))
    )
    (net (code "90") (name "/PRG0_PRU1GPO13") (class "Default")
      (node (ref "J18") (pin "46") (pinfunction "46_46") (pintype "passive"))
      (node (ref "RA16") (pin "4") (pinfunction "4_4") (pintype "passive"))
    )
    (net (code "91") (name "/PRG0_PRU1GPO13_R") (class "Default")
      (node (ref "RA16") (pin "5") (pinfunction "5_5") (pintype "passive"))
      (node (ref "U34") (pin "AD25") (pinfunction "PRG0_PRU1GPO13_AD25") (pintype "passive"))
    )
    (net (code "92") (name "/PRG0_PRU1GPO14") (class "Default")
      (node (ref "J18") (pin "44") (pinfunction "44_44") (pintype "passive"))
      (node (ref "RA16") (pin "3") (pinfunction "3_3") (pintype "passive"))
    )
    (net (code "93") (name "/PRG0_PRU1GPO14_R") (class "Default")
      (node (ref "RA16") (pin "6") (pinfunction "6_6") (pintype "passive"))
      (node (ref "U34") (pin "AD24") (pinfunction "PRG0_PRU1GPO14_AD24") (pintype "passive"))
    )
    (net (code "94") (name "/PRG0_PRU1GPO15") (class "Default")
      (node (ref "J18") (pin "42") (pinfunction "42_42") (pintype "passive"))
      (node (ref "RA16") (pin "2") (pinfunction "2_2") (pintype "passive"))
    )
    (net (code "95") (name "/PRG0_PRU1GPO15_R") (class "Default")
      (node (ref "RA16") (pin "7") (pinfunction "7_7") (pintype "passive"))
      (node (ref "U34") (pin "AE27") (pinfunction "PRG0_PRU1GPO15_AE27") (pintype "passive"))
    )
    (net (code "96") (name "/PRG0_PRU1GPO16") (class "Default")
      (node (ref "J18") (pin "38") (pinfunction "38_38") (pintype "passive"))
      (node (ref "RA16") (pin "1") (pinfunction "1_1") (pintype "passive"))
    )
    (net (code "97") (name "/PRG0_PRU1GPO16_R") (class "Default")
      (node (ref "RA16") (pin "8") (pinfunction "8_8") (pintype "passive"))
      (node (ref "U34") (pin "AC24") (pinfunction "PRG0_PRU1GPO16_AC24") (pintype "passive"))
    )
    (net (code "98") (name "/PRG0_PRU1GPO17") (class "Default")
      (node (ref "J18") (pin "24") (pinfunction "24_24") (pintype "passive"))
      (node (ref "U34") (pin "Y27") (pinfunction "PRG0_PRU1GPO17_Y27") (pintype "passive"))
    )
    (net (code "99") (name "/PRG0_PRU1GPO18") (class "Default")
      (node (ref "J18") (pin "51") (pinfunction "51_51") (pintype "passive"))
      (node (ref "U34") (pin "Y26") (pinfunction "PRG0_PRU1GPO18_Y26") (pintype "passive"))
    )
    (net (code "100") (name "/PRG0_PRU1GPO19") (class "Default")
      (node (ref "J18") (pin "47") (pinfunction "47_47") (pintype "passive"))
      (node (ref "U34") (pin "W26") (pinfunction "PRG0_PRU1GPO19_W26") (pintype "passive"))
    )
    (net (code "101") (name "/PRG0_RGMII1_ETH1_CLK") (class "Default")
      (node (ref "J18") (pin "4") (pinfunction "4_4") (pintype "passive"))
    )
    (net (code "102") (name "/PRG0_RGMII2_ETH2_CLK") (class "Default")
      (node (ref "J18") (pin "106") (pinfunction "106_106") (pintype "passive"))
    )
    (net (code "103") (name "/PRG1_MDIODATA") (class "Default")
      (node (ref "J18") (pin "99") (pinfunction "99_99") (pintype "passive"))
      (node (ref "R605") (pin "1") (pinfunction "1_1") (pintype "passive"))
      (node (ref "U34") (pin "AD18") (pinfunction "PRG1_MDIO0_MDIO_AD18") (pintype "passive"))
    )
    (net (code "104") (name "/PRG1_MDIOMDCLK") (class "Default")
      (node (ref "J18") (pin "95") (pinfunction "95_95") (pintype "passive"))
      (node (ref "U34") (pin "AH18") (pinfunction "PRG1_MDIO0_MDC_AH18") (pintype "passive"))
    )
    (net (code "105") (name "/PRG1_PRU0GPO0") (class "Default")
      (node (ref "J18") (pin "88") (pinfunction "88_88") (pintype "passive"))
      (node (ref "U34") (pin "AE22") (pinfunction "PRG1_PRU0GPO0_AE22") (pintype "passive"))
    )
    (net (code "106") (name "/PRG1_PRU0GPO1") (class "Default")
      (node (ref "J18") (pin "76") (pinfunction "76_76") (pintype "passive"))
      (node (ref "U34") (pin "AG24") (pinfunction "PRG1_PRU0GPO1_AG24") (pintype "passive"))
    )
    (net (code "107") (name "/PRG1_PRU0GPO2") (class "Default")
      (node (ref "J18") (pin "80") (pinfunction "80_80") (pintype "passive"))
      (node (ref "U34") (pin "AF23") (pinfunction "PRG1_PRU0GPO2_AF23") (pintype "passive"))
    )
    (net (code "108") (name "/PRG1_PRU0GPO3") (class "Default")
      (node (ref "J18") (pin "90") (pinfunction "90_90") (pintype "passive"))
      (node (ref "U34") (pin "AD21") (pinfunction "PRG1_PRU0GPO3_AD21") (pintype "passive"))
    )
    (net (code "109") (name "/PRG1_PRU0GPO4") (class "Default")
      (node (ref "J18") (pin "78") (pinfunction "78_78") (pintype "passive"))
      (node (ref "U34") (pin "AG23") (pinfunction "PRG1_PRU0GPO4_AG23") (pintype "passive"))
    )
    (net (code "110") (name "/PRG1_PRU0GPO5") (class "Default")
      (node (ref "J18") (pin "60") (pinfunction "60_60") (pintype "passive"))
      (node (ref "U34") (pin "AF27") (pinfunction "PRG1_PRU0GPO5_AF27") (pintype "passive"))
    )
    (net (code "111") (name "/PRG1_PRU0GPO6") (class "Default")
      (node (ref "J18") (pin "84") (pinfunction "84_84") (pintype "passive"))
      (node (ref "U34") (pin "AF22") (pinfunction "PRG1_PRU0GPO6_AF22") (pintype "passive"))
    )
    (net (code "112") (name "/PRG1_PRU0GPO7") (class "Default")
      (node (ref "J18") (pin "66") (pinfunction "66_66") (pintype "passive"))
      (node (ref "U34") (pin "AG27") (pinfunction "PRG1_PRU0GPO7_AG27") (pintype "passive"))
    )
    (net (code "113") (name "/PRG1_PRU0GPO8") (class "Default")
      (node (ref "J18") (pin "58") (pinfunction "58_58") (pintype "passive"))
      (node (ref "U34") (pin "AF28") (pinfunction "PRG1_PRU0GPO8_AF28") (pintype "passive"))
    )
    (net (code "114") (name "/PRG1_PRU0GPO9") (class "Default")
      (node (ref "J18") (pin "62") (pinfunction "62_62") (pintype "passive"))
      (node (ref "U34") (pin "AF26") (pinfunction "PRG1_PRU0GPO9_AF26") (pintype "passive"))
    )
    (net (code "115") (name "/PRG1_PRU0GPO10") (class "Default")
      (node (ref "J18") (pin "74") (pinfunction "74_74") (pintype "passive"))
      (node (ref "U34") (pin "AH25") (pinfunction "PRG1_PRU0GPO10_AH25") (pintype "passive"))
    )
    (net (code "116") (name "/PRG1_PRU0GPO11") (class "Default")
      (node (ref "J18") (pin "98") (pinfunction "98_98") (pintype "passive"))
      (node (ref "R508") (pin "2") (pinfunction "2_2") (pintype "passive"))
    )
    (net (code "117") (name "/PRG1_PRU0GPO12") (class "Default")
      (node (ref "J18") (pin "110") (pinfunction "110_110") (pintype "passive"))
      (node (ref "RA13") (pin "4") (pinfunction "4_4") (pintype "passive"))
    )
    (net (code "118") (name "/PRG1_PRU0GPO13") (class "Default")
      (node (ref "J18") (pin "114") (pinfunction "114_114") (pintype "passive"))
      (node (ref "RA13") (pin "3") (pinfunction "3_3") (pintype "passive"))
    )
    (net (code "119") (name "/PRG1_PRU0GPO14") (class "Default")
      (node (ref "J18") (pin "100") (pinfunction "100_100") (pintype "passive"))
      (node (ref "RA13") (pin "2") (pinfunction "2_2") (pintype "passive"))
    )
    (net (code "120") (name "/PRG1_PRU0GPO15") (class "Default")
      (node (ref "J18") (pin "102") (pinfunction "102_102") (pintype "passive"))
      (node (ref "RA13") (pin "1") (pinfunction "1_1") (pintype "passive"))
    )
    (net (code "121") (name "/PRG1_PRU0GPO16") (class "Default")
      (node (ref "J18") (pin "94") (pinfunction "94_94") (pintype "passive"))
      (node (ref "U34") (pin "AD20") (pinfunction "PRG1_PRU0GPO16_AD20") (pintype "passive"))
    )
    (net (code "122") (name "/PRG1_PRU0GPO17") (class "Default")
      (node (ref "J18") (pin "70") (pinfunction "70_70") (pintype "passive"))
      (node (ref "U34") (pin "AH26") (pinfunction "PRG1_PRU0GPO17_AH26") (pintype "passive"))
    )
    (net (code "123") (name "/PRG1_PRU0GPO18") (class "Default")
      (node (ref "J18") (pin "72") (pinfunction "72_72") (pintype "passive"))
      (node (ref "U34") (pin "AG25") (pinfunction "PRG1_PRU0GPO18_AG25") (pintype "passive"))
    )
    (net (code "124") (name "/PRG1_PRU0GPO19") (class "Default")
      (node (ref "J18") (pin "68") (pinfunction "68_68") (pintype "passive"))
      (node (ref "U34") (pin "AG26") (pinfunction "PRG1_PRU0GPO19_AG26") (pintype "passive"))
    )
    (net (code "125") (name "/PRG1_PRU0_GPO11_R") (class "Default")
      (node (ref "R508") (pin "1") (pinfunction "1_1") (pintype "passive"))
      (node (ref "U34") (pin "AF21") (pinfunction "PRG1_PRU0GPO11_AF21") (pintype "passive"))
    )
    (net (code "126") (name "/PRG1_PRU0_GPO12_R") (class "Default")
      (node (ref "RA13") (pin "5") (pinfunction "5_5") (pintype "passive"))
      (node (ref "U34") (pin "AH20") (pinfunction "PRG1_PRU0GPO12_AH20") (pintype "passive"))
    )
    (net (code "127") (name "/PRG1_PRU0_GPO13_R") (class "Default")
      (node (ref "RA13") (pin "6") (pinfunction "6_6") (pintype "passive"))
      (node (ref "U34") (pin "AH21") (pinfunction "PRG1_PRU0GPO13_AH21") (pintype "passive"))
    )
    (net (code "128") (name "/PRG1_PRU0_GPO14_R") (class "Default")
      (node (ref "RA13") (pin "7") (pinfunction "7_7") (pintype "passive"))
      (node (ref "U34") (pin "AG20") (pinfunction "PRG1_PRU0GPO14_AG20") (pintype "passive"))
    )
    (net (code "129") (name "/PRG1_PRU0_GPO15_R") (class "Default")
      (node (ref "RA13") (pin "8") (pinfunction "8_8") (pintype "passive"))
      (node (ref "U34") (pin "AD19") (pinfunction "PRG1_PRU0GPO15_AD19") (pintype "passive"))
    )
    (net (code "130") (name "/PRG1_PRU1GPO0") (class "Default")
      (node (ref "J18") (pin "63") (pinfunction "63_63") (pintype "passive"))
      (node (ref "U34") (pin "AH24") (pinfunction "PRG1_PRU1GPO0_AH24") (pintype "passive"))
    )
    (net (code "131") (name "/PRG1_PRU1GPO1") (class "Default")
      (node (ref "J18") (pin "67") (pinfunction "67_67") (pintype "passive"))
      (node (ref "U34") (pin "AH23") (pinfunction "PRG1_PRU1GPO1_AH23") (pintype "passive"))
    )
    (net (code "132") (name "/PRG1_PRU1GPO2") (class "Default")
      (node (ref "J18") (pin "77") (pinfunction "77_77") (pintype "passive"))
      (node (ref "U34") (pin "AG21") (pinfunction "PRG1_PRU1GPO2_AG21") (pintype "passive"))
    )
    (net (code "133") (name "/PRG1_PRU1GPO3") (class "Default")
      (node (ref "J18") (pin "75") (pinfunction "75_75") (pintype "passive"))
      (node (ref "U34") (pin "AH22") (pinfunction "PRG1_PRU1GPO3_AH22") (pintype "passive"))
    )
    (net (code "134") (name "/PRG1_PRU1GPO4") (class "Default")
      (node (ref "J18") (pin "65") (pinfunction "65_65") (pintype "passive"))
      (node (ref "U34") (pin "AE21") (pinfunction "PRG1_PRU1GPO4_AE21") (pintype "passive"))
    )
    (net (code "135") (name "/PRG1_PRU1GPO5") (class "Default")
      (node (ref "J18") (pin "55") (pinfunction "55_55") (pintype "passive"))
      (node (ref "U34") (pin "AC22") (pinfunction "PRG1_PRU1GPO5_AC22") (pintype "passive"))
    )
    (net (code "136") (name "/PRG1_PRU1GPO6") (class "Default")
      (node (ref "J18") (pin "71") (pinfunction "71_71") (pintype "passive"))
      (node (ref "U34") (pin "AG22") (pinfunction "PRG1_PRU1GPO6_AG22") (pintype "passive"))
    )
    (net (code "137") (name "/PRG1_PRU1GPO8") (class "Default")
      (node (ref "J18") (pin "57") (pinfunction "57_57") (pintype "passive"))
      (node (ref "U34") (pin "AE24") (pinfunction "PRG1_PRU1GPO8_AE24") (pintype "passive"))
    )
    (net (code "138") (name "/PRG1_PRU1GPO9") (class "Default")
      (node (ref "J18") (pin "64") (pinfunction "64_64") (pintype "passive"))
      (node (ref "U34") (pin "AF25") (pinfunction "PRG1_PRU1GPO9_AF25") (pintype "passive"))
    )
    (net (code "139") (name "/PRG1_PRU1GPO10") (class "Default")
      (node (ref "J18") (pin "61") (pinfunction "61_61") (pintype "passive"))
      (node (ref "U34") (pin "AF24") (pinfunction "PRG1_PRU1GPO10_AF24") (pintype "passive"))
    )
    (net (code "140") (name "/PRG1_PRU1GPO11") (class "Default")
      (node (ref "J18") (pin "81") (pinfunction "81_81") (pintype "passive"))
      (node (ref "R499") (pin "2") (pinfunction "2_2") (pintype "passive"))
    )
    (net (code "141") (name "/PRG1_PRU1GPO11_R") (class "Default")
      (node (ref "R499") (pin "1") (pinfunction "1_1") (pintype "passive"))
      (node (ref "U34") (pin "AC20") (pinfunction "PRG1_PRU1GPO11_AC20") (pintype "passive"))
    )
    (net (code "142") (name "/PRG1_PRU1GPO12") (class "Default")
      (node (ref "J18") (pin "79") (pinfunction "79_79") (pintype "passive"))
      (node (ref "R505") (pin "2") (pinfunction "2_2") (pintype "passive"))
    )
    (net (code "143") (name "/PRG1_PRU1GPO12_R") (class "Default")
      (node (ref "R505") (pin "1") (pinfunction "1_1") (pintype "passive"))
      (node (ref "U34") (pin "AE20") (pinfunction "PRG1_PRU1GPO12_AE20") (pintype "passive"))
    )
    (net (code "144") (name "/PRG1_PRU1GPO13") (class "Default")
      (node (ref "J18") (pin "91") (pinfunction "91_91") (pintype "passive"))
      (node (ref "RA12") (pin "4") (pinfunction "4_4") (pintype "passive"))
    )
    (net (code "145") (name "/PRG1_PRU1GPO13_R") (class "Default")
      (node (ref "RA12") (pin "5") (pinfunction "5_5") (pintype "passive"))
      (node (ref "U34") (pin "AF19") (pinfunction "PRG1_PRU1GPO13_AF19") (pintype "passive"))
    )
    (net (code "146") (name "/PRG1_PRU1GPO14") (class "Default")
      (node (ref "J18") (pin "93") (pinfunction "93_93") (pintype "passive"))
      (node (ref "RA12") (pin "3") (pinfunction "3_3") (pintype "passive"))
    )
    (net (code "147") (name "/PRG1_PRU1GPO14_R") (class "Default")
      (node (ref "RA12") (pin "6") (pinfunction "6_6") (pintype "passive"))
      (node (ref "U34") (pin "AH19") (pinfunction "PRG1_PRU1GPO14_AH19") (pintype "passive"))
    )
    (net (code "148") (name "/PRG1_PRU1GPO15") (class "Default")
      (node (ref "J18") (pin "83") (pinfunction "83_83") (pintype "passive"))
      (node (ref "RA12") (pin "2") (pinfunction "2_2") (pintype "passive"))
    )
    (net (code "149") (name "/PRG1_PRU1GPO15_R") (class "Default")
      (node (ref "RA12") (pin "7") (pinfunction "7_7") (pintype "passive"))
      (node (ref "U34") (pin "AG19") (pinfunction "PRG1_PRU1GPO15_AG19") (pintype "passive"))
    )
    (net (code "150") (name "/PRG1_PRU1GPO16") (class "Default")
      (node (ref "J18") (pin "87") (pinfunction "87_87") (pintype "passive"))
      (node (ref "RA12") (pin "1") (pinfunction "1_1") (pintype "passive"))
    )
    (net (code "151") (name "/PRG1_PRU1GPO16_R") (class "Default")
      (node (ref "RA12") (pin "8") (pinfunction "8_8") (pintype "passive"))
      (node (ref "U34") (pin "AE19") (pinfunction "PRG1_PRU1GPO16_AE19") (pintype "passive"))
    )
    (net (code "152") (name "/PRG1_RGMII1_ETH1_CLK") (class "Default")
      (node (ref "J18") (pin "3") (pinfunction "3_3") (pintype "passive"))
    )
    (net (code "153") (name "/PRG1_RGMII2_ETH2_CLK") (class "Default")
      (node (ref "J18") (pin "103") (pinfunction "103_103") (pintype "passive"))
    )
    (net (code "154") (name "/SOC_I2C0_SCL") (class "Default")
      (node (ref "J16") (pin "21") (pinfunction "21_21") (pintype "passive"))
    )
    (net (code "155") (name "/SOC_I2C0_SDA") (class "Default")
      (node (ref "J16") (pin "23") (pinfunction "23_23") (pintype "passive"))
    )
    (net (code "156") (name "/SOC_MAIN_UART1_RX_1V8") (class "Default")
      (node (ref "U34") (pin "AE23") (pinfunction "PRG1_PRU1GPO17_AE23") (pintype "passive"))
    )
    (net (code "157") (name "/SOC_MAIN_UART1_TX_1V8") (class "Default")
      (node (ref "U34") (pin "AD23") (pinfunction "PRG1_PRU1GPO7_AD23") (pintype "passive"))
    )
    (net (code "158") (name "/SOC_SPI0_CLK") (class "Default")
      (node (ref "J16") (pin "20") (pinfunction "20_20") (pintype "passive"))
    )
    (net (code "159") (name "/SOC_SPI0_CS1") (class "Default")
      (node (ref "J16") (pin "24") (pinfunction "24_24") (pintype "passive"))
    )
    (net (code "160") (name "/SOC_SPI0_D0") (class "Default")
      (node (ref "J16") (pin "26") (pinfunction "26_26") (pintype "passive"))
    )
    (net (code "161") (name "/SOC_SPI0_D1") (class "Default")
      (node (ref "J16") (pin "28") (pinfunction "28_28") (pintype "passive"))
    )
    (net (code "162") (name "/SOC_UART1_CTS_1V8") (class "Default")
      (node (ref "U34") (pin "AD22") (pinfunction "PRG1_PRU1GPO18_AD22") (pintype "passive"))
    )
    (net (code "163") (name "/SOC_UART1_RTS_1V8") (class "Default")
      (node (ref "U34") (pin "AC21") (pinfunction "PRG1_PRU1GPO19_AC21") (pintype "passive"))
    )
    (net (code "164") (name "/SOC_WKUP_SCL") (class "Default")
      (node (ref "J16") (pin "15") (pinfunction "15_15") (pintype "passive"))
    )
    (net (code "165") (name "/SOC_WKUP_SDA") (class "Default")
      (node (ref "J16") (pin "17") (pinfunction "17_17") (pintype "passive"))
    )
    (net (code "166") (name "DGND") (class "Default")
      (node (ref "C213") (pin "2") (pinfunction "2_2") (pintype "passive"))
      (node (ref "C215") (pin "2") (pinfunction "2_2") (pintype "passive"))
      (node (ref "C216") (pin "2") (pinfunction "2_2") (pintype "passive"))
      (node (ref "C222") (pin "2") (pinfunction "2_2") (pintype "passive"))
      (node (ref "C223") (pin "2") (pinfunction "2_2") (pintype "passive"))
      (node (ref "C227") (pin "2") (pinfunction "2_2") (pintype "passive"))
      (node (ref "C228") (pin "2") (pinfunction "2_2") (pintype "passive"))
      (node (ref "C609") (pin "2") (pinfunction "2_2") (pintype "passive"))
      (node (ref "C612") (pin "2") (pinfunction "2_2") (pintype "passive"))
      (node (ref "C73") (pin "2") (pinfunction "2_2") (pintype "passive"))
      (node (ref "C74") (pin "2") (pinfunction "2_2") (pintype "passive"))
      (node (ref "C75") (pin "2") (pinfunction "2_2") (pintype "passive"))
      (node (ref "C76") (pin "2") (pinfunction "2_2") (pintype "passive"))
      (node (ref "J10") (pin "1") (pinfunction "1_1") (pintype "passive"))
      (node (ref "J10") (pin "13") (pinfunction "13_13") (pintype "passive"))
      (node (ref "J10") (pin "14") (pinfunction "14_14") (pintype "passive"))
      (node (ref "J10") (pin "19") (pinfunction "19_19") (pintype "passive"))
      (node (ref "J10") (pin "20") (pinfunction "20_20") (pintype "passive"))
      (node (ref "J10") (pin "7") (pinfunction "7_7") (pintype "passive"))
      (node (ref "J10") (pin "8") (pinfunction "8_8") (pintype "passive"))
      (node (ref "J16") (pin "13") (pinfunction "13_13") (pintype "passive"))
      (node (ref "J16") (pin "18") (pinfunction "18_18") (pintype "passive"))
      (node (ref "J16") (pin "19") (pinfunction "19_19") (pintype "passive"))
      (node (ref "J16") (pin "22") (pinfunction "22_22") (pintype "passive"))
      (node (ref "J16") (pin "25") (pinfunction "25_25") (pintype "passive"))
      (node (ref "J16") (pin "40") (pinfunction "40_40") (pintype "passive"))
      (node (ref "J16") (pin "44") (pinfunction "44_44") (pintype "passive"))
      (node (ref "J16") (pin "61") (pinfunction "61_61") (pintype "passive"))
      (node (ref "J16") (pin "62") (pinfunction "62_62") (pintype "passive"))
      (node (ref "J16") (pin "63") (pinfunction "63_63") (pintype "passive"))
      (node (ref "J16") (pin "64") (pinfunction "64_64") (pintype "passive"))
      (node (ref "J18") (pin "1") (pinfunction "1_1") (pintype "passive"))
      (node (ref "J18") (pin "101") (pinfunction "101_101") (pintype "passive"))
      (node (ref "J18") (pin "104") (pinfunction "104_104") (pintype "passive"))
      (node (ref "J18") (pin "105") (pinfunction "105_105") (pintype "passive"))
      (node (ref "J18") (pin "107") (pinfunction "107_107") (pintype "passive"))
      (node (ref "J18") (pin "108") (pinfunction "108_108") (pintype "passive"))
      (node (ref "J18") (pin "109") (pinfunction "109_109") (pintype "passive"))
      (node (ref "J18") (pin "111") (pinfunction "111_111") (pintype "passive"))
      (node (ref "J18") (pin "112") (pinfunction "112_112") (pintype "passive"))
      (node (ref "J18") (pin "115") (pinfunction "115_115") (pintype "passive"))
      (node (ref "J18") (pin "116") (pinfunction "116_116") (pintype "passive"))
      (node (ref "J18") (pin "117") (pinfunction "117_117") (pintype "passive"))
      (node (ref "J18") (pin "118") (pinfunction "118_118") (pintype "passive"))
      (node (ref "J18") (pin "119") (pinfunction "119_119") (pintype "passive"))
      (node (ref "J18") (pin "120") (pinfunction "120_120") (pintype "passive"))
      (node (ref "J18") (pin "121") (pinfunction "121_121") (pintype "passive"))
      (node (ref "J18") (pin "122") (pinfunction "122_122") (pintype "passive"))
      (node (ref "J18") (pin "123") (pinfunction "123_123") (pintype "passive"))
      (node (ref "J18") (pin "124") (pinfunction "124_124") (pintype "passive"))
      (node (ref "J18") (pin "125") (pinfunction "125_125") (pintype "passive"))
      (node (ref "J18") (pin "126") (pinfunction "126_126") (pintype "passive"))
      (node (ref "J18") (pin "127") (pinfunction "127_127") (pintype "passive"))
      (node (ref "J18") (pin "128") (pinfunction "128_128") (pintype "passive"))
      (node (ref "J18") (pin "17") (pinfunction "17_17") (pintype "passive"))
      (node (ref "J18") (pin "2") (pinfunction "2_2") (pintype "passive"))
      (node (ref "J18") (pin "21") (pinfunction "21_21") (pintype "passive"))
      (node (ref "J18") (pin "25") (pinfunction "25_25") (pintype "passive"))
      (node (ref "J18") (pin "29") (pinfunction "29_29") (pintype "passive"))
      (node (ref "J18") (pin "36") (pinfunction "36_36") (pintype "passive"))
      (node (ref "J18") (pin "40") (pinfunction "40_40") (pintype "passive"))
      (node (ref "J18") (pin "5") (pinfunction "5_5") (pintype "passive"))
      (node (ref "J18") (pin "52") (pinfunction "52_52") (pintype "passive"))
      (node (ref "J18") (pin "56") (pinfunction "56_56") (pintype "passive"))
      (node (ref "J18") (pin "6") (pinfunction "6_6") (pintype "passive"))
      (node (ref "J18") (pin "69") (pinfunction "69_69") (pintype "passive"))
      (node (ref "J18") (pin "73") (pinfunction "73_73") (pintype "passive"))
      (node (ref "J18") (pin "82") (pinfunction "82_82") (pintype "passive"))
      (node (ref "J18") (pin "85") (pinfunction "85_85") (pintype "passive"))
      (node (ref "J18") (pin "86") (pinfunction "86_86") (pintype "passive"))
      (node (ref "J18") (pin "89") (pinfunction "89_89") (pintype "passive"))
      (node (ref "J18") (pin "92") (pinfunction "92_92") (pintype "passive"))
      (node (ref "J18") (pin "96") (pinfunction "96_96") (pintype "passive"))
      (node (ref "J18") (pin "97") (pinfunction "97_97") (pintype "passive"))
    )
    (net (code "167") (name "VCC1V8") (class "Default")
      (node (ref "C213") (pin "1") (pinfunction "1_1") (pintype "passive"))
      (node (ref "C216") (pin "1") (pinfunction "1_1") (pintype "passive"))
      (node (ref "J16") (pin "55") (pinfunction "55_55") (pintype "passive"))
      (node (ref "J16") (pin "57") (pinfunction "57_57") (pintype "passive"))
      (node (ref "J16") (pin "59") (pinfunction "59_59") (pintype "passive"))
      (node (ref "R307") (pin "2") (pinfunction "2_2") (pintype "passive"))
      (node (ref "R605") (pin "2") (pinfunction "2_2") (pintype "passive"))
    )
    (net (code "168") (name "VCC3V3_IO") (class "Default")
      (node (ref "C222") (pin "1") (pinfunction "1_1") (pintype "passive"))
      (node (ref "C227") (pin "1") (pinfunction "1_1") (pintype "passive"))
      (node (ref "J16") (pin "1") (pinfunction "1_1") (pintype "passive"))
      (node (ref "J16") (pin "3") (pinfunction "3_3") (pintype "passive"))
      (node (ref "J16") (pin "5") (pinfunction "5_5") (pintype "passive"))
    )
    (net (code "169") (name "VCC_5V0") (class "Default")
      (node (ref "C223") (pin "1") (pinfunction "1_1") (pintype "passive"))
      (node (ref "C228") (pin "1") (pinfunction "1_1") (pintype "passive"))
      (node (ref "J16") (pin "2") (pinfunction "2_2") (pintype "passive"))
      (node (ref "J16") (pin "4") (pinfunction "4_4") (pintype "passive"))
      (node (ref "J16") (pin "6") (pinfunction "6_6") (pintype "passive"))
    )
    (net (code "170") (name "VDD_1V0") (class "Default")
      (node (ref "C215") (pin "1") (pinfunction "1_1") (pintype "passive"))
      (node (ref "J16") (pin "56") (pinfunction "56_56") (pintype "passive"))
      (node (ref "J16") (pin "58") (pinfunction "58_58") (pintype "passive"))
      (node (ref "J16") (pin "60") (pinfunction "60_60") (pintype "passive"))
    )
    (net (code "171") (name "VDD_2V5") (class "Default")
      (node (ref "C609") (pin "1") (pinfunction "1_1") (pintype "passive"))
      (node (ref "C612") (pin "1") (pinfunction "1_1") (pintype "passive"))
      (node (ref "J16") (pin "52") (pinfunction "52_52") (pintype "passive"))
      (node (ref "J16") (pin "54") (pinfunction "54_54") (pintype "passive"))
    )
    (net (code "172") (name "unconnected-(J16-Pad7)") (class "Default")
      (node (ref "J16") (pin "7") (pinfunction "7_7") (pintype "passive"))
    )
    (net (code "173") (name "unconnected-(J16-Pad8)") (class "Default")
      (node (ref "J16") (pin "8") (pinfunction "8_8") (pintype "passive"))
    )
    (net (code "174") (name "unconnected-(J16-Pad9)") (class "Default")
      (node (ref "J16") (pin "9") (pinfunction "9_9") (pintype "passive"))
    )
    (net (code "175") (name "unconnected-(J16-Pad10)") (class "Default")
      (node (ref "J16") (pin "10") (pinfunction "10_10") (pintype "passive"))
    )
    (net (code "176") (name "unconnected-(J16-Pad11)") (class "Default")
      (node (ref "J16") (pin "11") (pinfunction "11_11") (pintype "passive"))
    )
    (net (code "177") (name "unconnected-(J16-Pad12)") (class "Default")
      (node (ref "J16") (pin "12") (pinfunction "12_12") (pintype "passive"))
    )
    (net (code "178") (name "unconnected-(J16-Pad14)") (class "Default")
      (node (ref "J16") (pin "14") (pinfunction "14_14") (pintype "passive"))
    )
    (net (code "179") (name "unconnected-(J16-Pad16)") (class "Default")
      (node (ref "J16") (pin "16") (pinfunction "16_16") (pintype "passive"))
    )
    (net (code "180") (name "unconnected-(J16-Pad35)") (class "Default")
      (node (ref "J16") (pin "35") (pinfunction "35_35") (pintype "passive"))
    )
    (net (code "181") (name "unconnected-(J16-Pad37)") (class "Default")
      (node (ref "J16") (pin "37") (pinfunction "37_37") (pintype "passive"))
    )
    (net (code "182") (name "unconnected-(J16-Pad39)") (class "Default")
      (node (ref "J16") (pin "39") (pinfunction "39_39") (pintype "passive"))
    )
    (net (code "183") (name "unconnected-(J16-Pad41)") (class "Default")
      (node (ref "J16") (pin "41") (pinfunction "41_41") (pintype "passive"))
    )
    (net (code "184") (name "unconnected-(J16-Pad43)") (class "Default")
      (node (ref "J16") (pin "43") (pinfunction "43_43") (pintype "passive"))
    )
    (net (code "185") (name "unconnected-(J16-Pad45)") (class "Default")
      (node (ref "J16") (pin "45") (pinfunction "45_45") (pintype "passive"))
    )
    (net (code "186") (name "unconnected-(J16-Pad46)") (class "Default")
      (node (ref "J16") (pin "46") (pinfunction "46_46") (pintype "passive"))
    )
    (net (code "187") (name "unconnected-(J16-Pad47)") (class "Default")
      (node (ref "J16") (pin "47") (pinfunction "47_47") (pintype "passive"))
    )
    (net (code "188") (name "unconnected-(J16-Pad48)") (class "Default")
      (node (ref "J16") (pin "48") (pinfunction "48_48") (pintype "passive"))
    )
    (net (code "189") (name "unconnected-(J16-Pad49)") (class "Default")
      (node (ref "J16") (pin "49") (pinfunction "49_49") (pintype "passive"))
    )
    (net (code "190") (name "unconnected-(J16-Pad50)") (class "Default")
      (node (ref "J16") (pin "50") (pinfunction "50_50") (pintype "passive"))
    )
    (net (code "191") (name "unconnected-(J16-Pad51)") (class "Default")
      (node (ref "J16") (pin "51") (pinfunction "51_51") (pintype "passive"))
    )
    (net (code "192") (name "unconnected-(J16-Pad53)") (class "Default")
      (node (ref "J16") (pin "53") (pinfunction "53_53") (pintype "passive"))
    )
  )
)
